# purple-eye.net
KiCad netlist of a schematic drawn in EAGLE
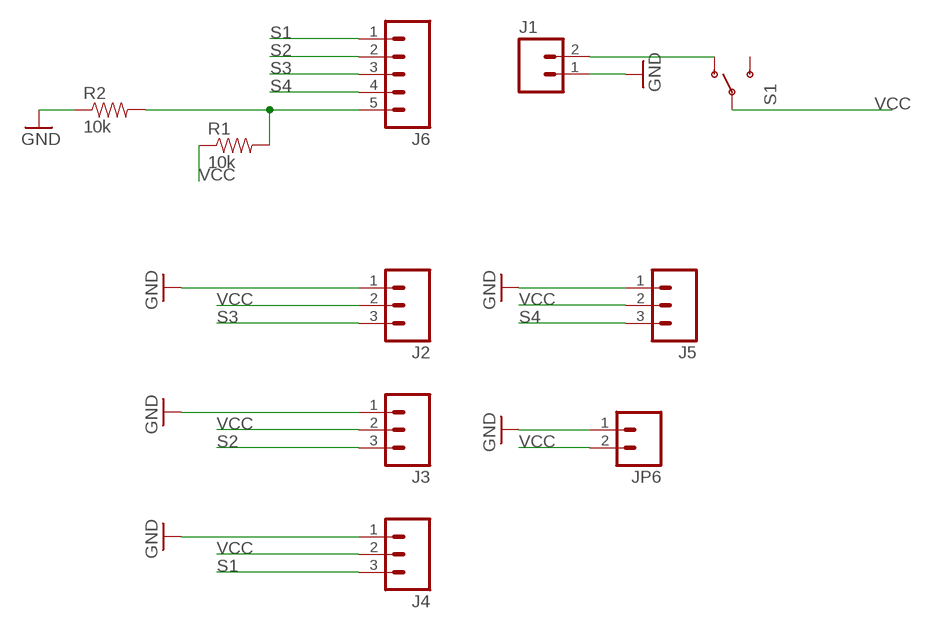
[diagram p0: schematic, sheet 1]

(export (version "E")
  (design (tool "Eeschema 10.0.6"))
  (components
    (comp (ref "J1")
      (value "M02JST-PTH-2")
      (footprint "eagle-import:JST-2-PTH")
      (libsource (lib "eagle-import") (part "M02JST-PTH-2"))
    )
    (comp (ref "J2")
      (value "M03LOCK")
      (footprint "eagle-import:1X03_LOCK")
      (libsource (lib "eagle-import") (part "M03LOCK"))
    )
    (comp (ref "J3")
      (value "M03LOCK")
      (footprint "eagle-import:1X03_LOCK")
      (libsource (lib "eagle-import") (part "M03LOCK"))
    )
    (comp (ref "J4")
      (value "M03LOCK")
      (footprint "eagle-import:1X03_LOCK")
      (libsource (lib "eagle-import") (part "M03LOCK"))
    )
    (comp (ref "J5")
      (value "M03LOCK")
      (footprint "eagle-import:1X03_LOCK")
      (libsource (lib "eagle-import") (part "M03LOCK"))
    )
    (comp (ref "J6")
      (value "M05LOCK")
      (footprint "eagle-import:1X05_LOCK")
      (libsource (lib "eagle-import") (part "M05LOCK"))
    )
    (comp (ref "JP6")
      (value "M02LOCK")
      (footprint "eagle-import:1X02_LOCK")
      (libsource (lib "eagle-import") (part "M02LOCK"))
    )
    (comp (ref "R1")
      (value "10k")
      (footprint "eagle-import:AXIAL-0.3EZ")
      (libsource (lib "eagle-import") (part "10KOHM-1/4W5%(PTH)HORIZ-KIT"))
    )
    (comp (ref "R2")
      (value "10k")
      (footprint "eagle-import:AXIAL-0.3EZ")
      (libsource (lib "eagle-import") (part "10KOHM-1/4W5%(PTH)HORIZ-KIT"))
    )
    (comp (ref "S1")
      (value "SWITCH-SPDTPTH_LOCK")
      (footprint "eagle-import:SWITCH-SPDT_LOCK.007S")
      (libsource (lib "eagle-import") (part "SWITCH-SPDTPTH_LOCK"))
    )
  )
  (nets
    (net (code "1") (name "/S1") (class "Default")
      (node (ref "J4") (pin "3") (pinfunction "3_3") (pintype "passive"))
      (node (ref "J6") (pin "1") (pinfunction "1_1") (pintype "passive"))
    )
    (net (code "2") (name "/S2") (class "Default")
      (node (ref "J3") (pin "3") (pinfunction "3_3") (pintype "passive"))
      (node (ref "J6") (pin "2") (pinfunction "2_2") (pintype "passive"))
    )
    (net (code "3") (name "/S3") (class "Default")
      (node (ref "J2") (pin "3") (pinfunction "3_3") (pintype "passive"))
      (node (ref "J6") (pin "3") (pinfunction "3_3") (pintype "passive"))
    )
    (net (code "4") (name "/S4") (class "Default")
      (node (ref "J5") (pin "3") (pinfunction "3_3") (pintype "passive"))
      (node (ref "J6") (pin "4") (pinfunction "4_4") (pintype "passive"))
    )
    (net (code "5") (name "/VCC") (class "Default")
      (node (ref "J2") (pin "2") (pinfunction "2_2") (pintype "passive"))
      (node (ref "J3") (pin "2") (pinfunction "2_2") (pintype "passive"))
      (node (ref "J4") (pin "2") (pinfunction "2_2") (pintype "passive"))
      (node (ref "J5") (pin "2") (pinfunction "2_2") (pintype "passive"))
      (node (ref "JP6") (pin "2") (pinfunction "2_2") (pintype "passive"))
      (node (ref "R1") (pin "P$1") (pinfunction "1_P$1") (pintype "passive"))
      (node (ref "S1") (pin "2") (pinfunction "P_2") (pintype "passive"))
    )
    (net (code "6") (name "GND") (class "Default")
      (node (ref "J1") (pin "1") (pinfunction "1_1") (pintype "passive"))
      (node (ref "J2") (pin "1") (pinfunction "1_1") (pintype "passive"))
      (node (ref "J3") (pin "1") (pinfunction "1_1") (pintype "passive"))
      (node (ref "J4") (pin "1") (pinfunction "1_1") (pintype "passive"))
      (node (ref "J5") (pin "1") (pinfunction "1_1") (pintype "passive"))
      (node (ref "JP6") (pin "1") (pinfunction "1_1") (pintype "passive"))
      (node (ref "R2") (pin "P$1") (pinfunction "1_P$1") (pintype "passive"))
    )
    (net (code "7") (name "Net-(R1-2)") (class "Default")
      (node (ref "J6") (pin "5") (pinfunction "5_5") (pintype "passive"))
      (node (ref "R1") (pin "P$2") (pinfunction "2_P$2") (pintype "passive"))
      (node (ref "R2") (pin "P$2") (pinfunction "2_P$2") (pintype "passive"))
    )
    (net (code "8") (name "Net-(S1-O)") (class "Default")
      (node (ref "J1") (pin "2") (pinfunction "2_2") (pintype "passive"))
      (node (ref "S1") (pin "1") (pinfunction "O_1") (pintype "passive"))
    )
    (net (code "9") (name "unconnected-(S1-S-Pad3)") (class "Default")
      (node (ref "S1") (pin "3") (pinfunction "S_3") (pintype "passive"))
    )
  )
)
